# ai_breakout_mics2714_panel.net
KiCad netlist of a schematic drawn in EAGLE
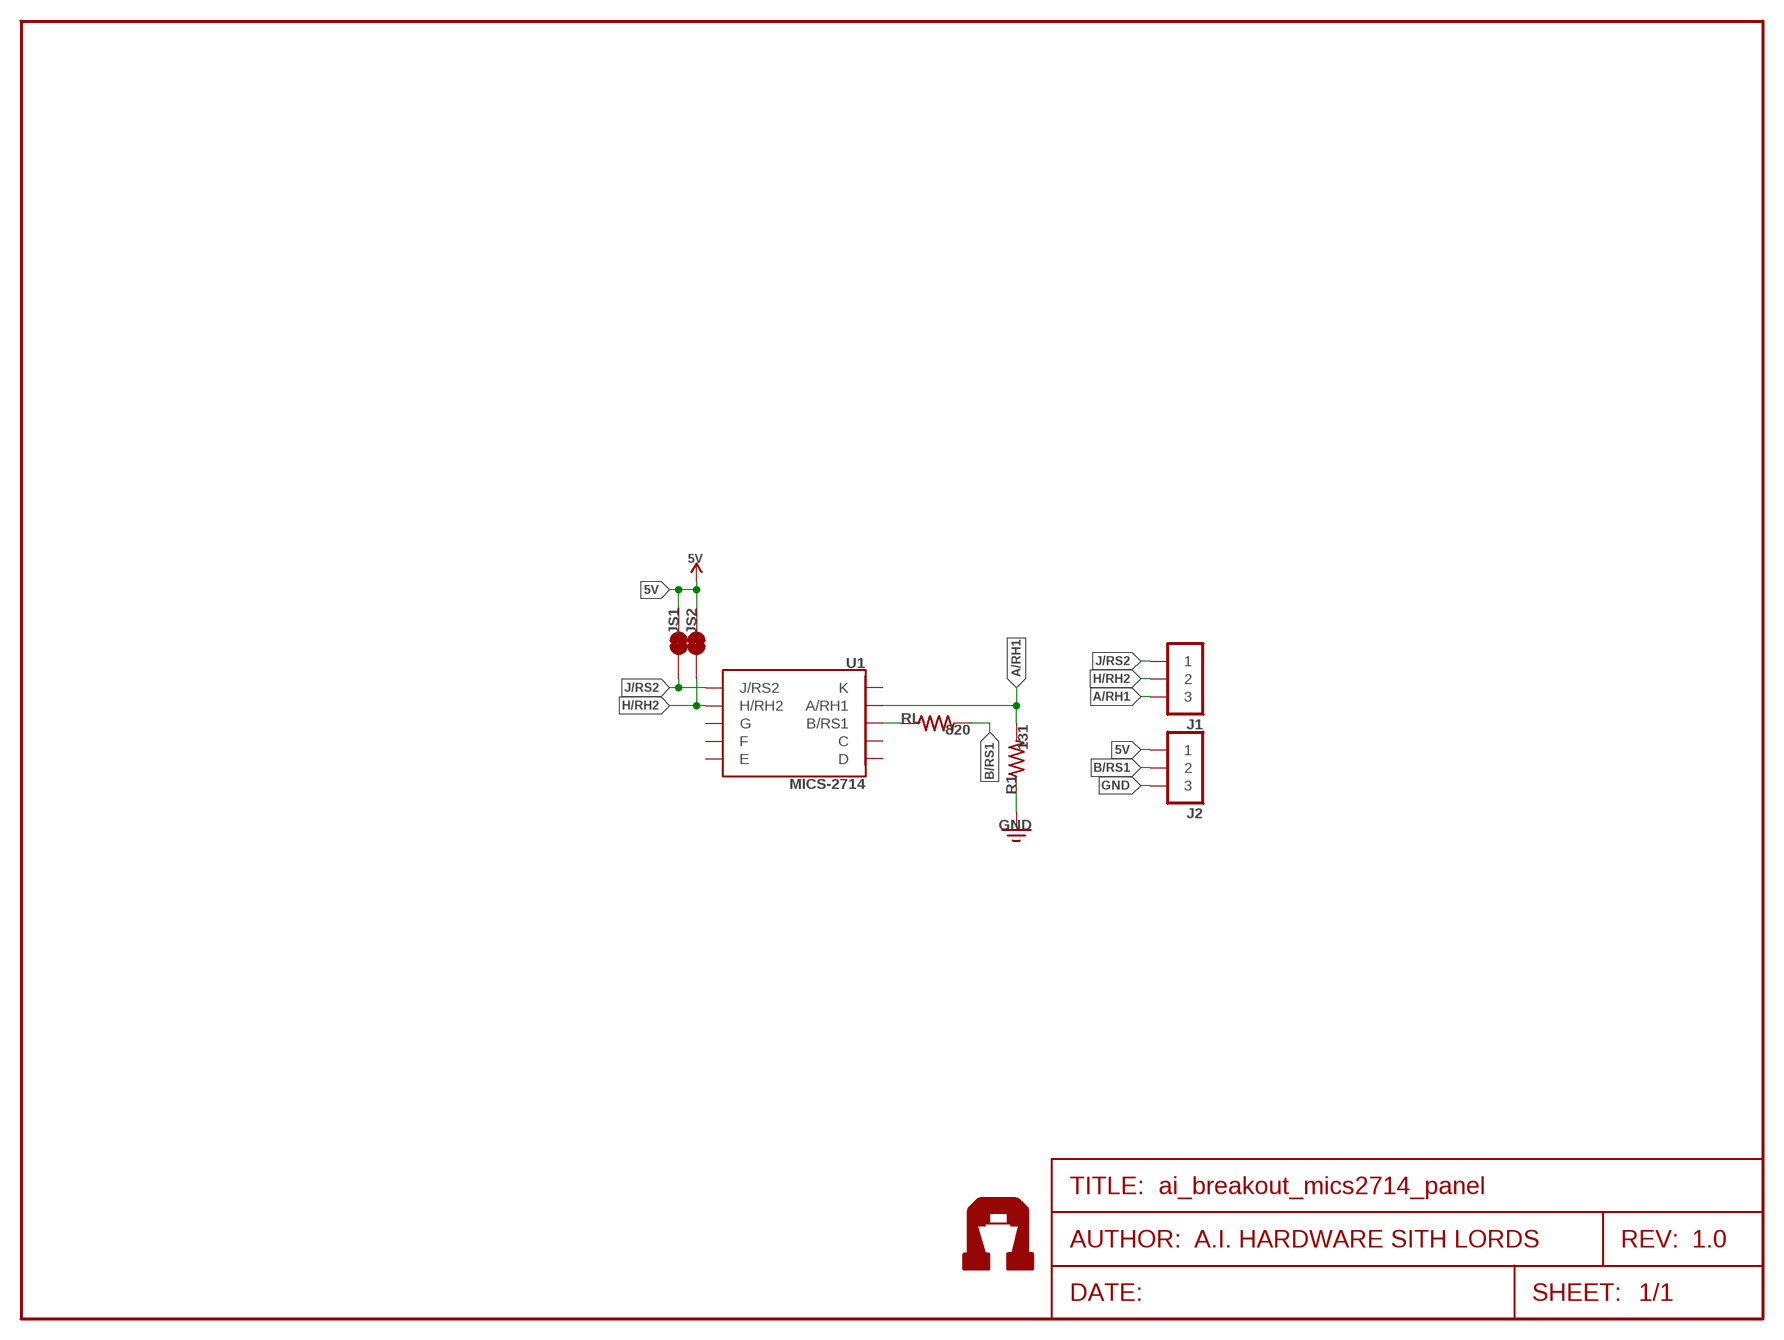
[diagram p0: schematic, sheet 1]

(export (version "E")
  (design (tool "Eeschema 10.0.6"))
  (components
    (comp (ref "J1")
      (value "1X03NOFIRST")
      (footprint "eagle-import:1X03-NOFIRST")
      (libsource (lib "eagle-import") (part "1X03NOFIRST"))
    )
    (comp (ref "J2")
      (value "1X03NOFIRST")
      (footprint "eagle-import:1X03-NOFIRST")
      (libsource (lib "eagle-import") (part "1X03NOFIRST"))
    )
    (comp (ref "JS1")
      (value "1X02-SJ-NCT")
      (footprint "eagle-import:1X02-SJ-NCT")
      (libsource (lib "eagle-import") (part "1X02-SJ-NCT"))
    )
    (comp (ref "JS2")
      (value "1X02-SJ-NCT")
      (footprint "eagle-import:1X02-SJ-NCT")
      (libsource (lib "eagle-import") (part "1X02-SJ-NCT"))
    )
    (comp (ref "R1")
      (value "131")
      (footprint "eagle-import:RES-0603")
      (libsource (lib "eagle-import") (part "RES0603"))
    )
    (comp (ref "RL")
      (value "820")
      (footprint "eagle-import:RES-0603")
      (libsource (lib "eagle-import") (part "RES0603"))
    )
    (comp (ref "U$3")
      (value "AI-LOGOXS")
      (footprint "eagle-import:AI-LOGO-XS")
      (libsource (lib "eagle-import") (part "AI-LOGOXS"))
    )
    (comp (ref "U1")
      (value "MICS-2714")
      (footprint "eagle-import:MICS-2714")
      (libsource (lib "eagle-import") (part "MICS-2714"))
    )
  )
  (nets
    (net (code "1") (name "5V") (class "Default")
      (node (ref "J2") (pin "1") (pinfunction "1_1") (pintype "bidirectional"))
      (node (ref "JS1") (pin "2") (pinfunction "2_2") (pintype "passive"))
      (node (ref "JS2") (pin "2") (pinfunction "2_2") (pintype "passive"))
    )
    (net (code "2") (name "A{slash}RH1") (class "Default")
      (node (ref "J1") (pin "3") (pinfunction "3_3") (pintype "bidirectional"))
      (node (ref "R1") (pin "2") (pinfunction "2_2") (pintype "passive"))
      (node (ref "U1") (pin "A") (pinfunction "A/RH1_A") (pintype "bidirectional"))
    )
    (net (code "3") (name "B{slash}RS1") (class "Default")
      (node (ref "J2") (pin "2") (pinfunction "2_2") (pintype "bidirectional"))
      (node (ref "RL") (pin "2") (pinfunction "2_2") (pintype "passive"))
    )
    (net (code "4") (name "GND") (class "Default")
      (node (ref "J2") (pin "3") (pinfunction "3_3") (pintype "bidirectional"))
      (node (ref "R1") (pin "1") (pinfunction "1_1") (pintype "passive"))
    )
    (net (code "5") (name "H{slash}RH2") (class "Default")
      (node (ref "J1") (pin "2") (pinfunction "2_2") (pintype "bidirectional"))
      (node (ref "JS2") (pin "1") (pinfunction "1_1") (pintype "passive"))
      (node (ref "U1") (pin "H") (pinfunction "H/RH2_H") (pintype "bidirectional"))
    )
    (net (code "6") (name "J{slash}RS2") (class "Default")
      (node (ref "J1") (pin "1") (pinfunction "1_1") (pintype "bidirectional"))
      (node (ref "JS1") (pin "1") (pinfunction "1_1") (pintype "passive"))
      (node (ref "U1") (pin "J") (pinfunction "J/RS2_J") (pintype "bidirectional"))
    )
    (net (code "7") (name "Net-(U1-B{slash}RS1)") (class "Default")
      (node (ref "RL") (pin "1") (pinfunction "1_1") (pintype "passive"))
      (node (ref "U1") (pin "B") (pinfunction "B/RS1_B") (pintype "bidirectional"))
    )
    (net (code "8") (name "unconnected-(U1-PadC)") (class "Default")
      (node (ref "U1") (pin "C") (pinfunction "C_C") (pintype "bidirectional"))
    )
    (net (code "9") (name "unconnected-(U1-PadD)") (class "Default")
      (node (ref "U1") (pin "D") (pinfunction "D_D") (pintype "bidirectional"))
    )
    (net (code "10") (name "unconnected-(U1-PadE)") (class "Default")
      (node (ref "U1") (pin "E") (pinfunction "E_E") (pintype "bidirectional"))
    )
    (net (code "11") (name "unconnected-(U1-PadF)") (class "Default")
      (node (ref "U1") (pin "F") (pinfunction "F_F") (pintype "bidirectional"))
    )
    (net (code "12") (name "unconnected-(U1-PadG)") (class "Default")
      (node (ref "U1") (pin "G") (pinfunction "G_G") (pintype "bidirectional"))
    )
    (net (code "13") (name "unconnected-(U1-PadK)") (class "Default")
      (node (ref "U1") (pin "K") (pinfunction "K_K") (pintype "bidirectional"))
    )
  )
)
